# BLEModule.net
KiCad netlist of a schematic drawn in EAGLE
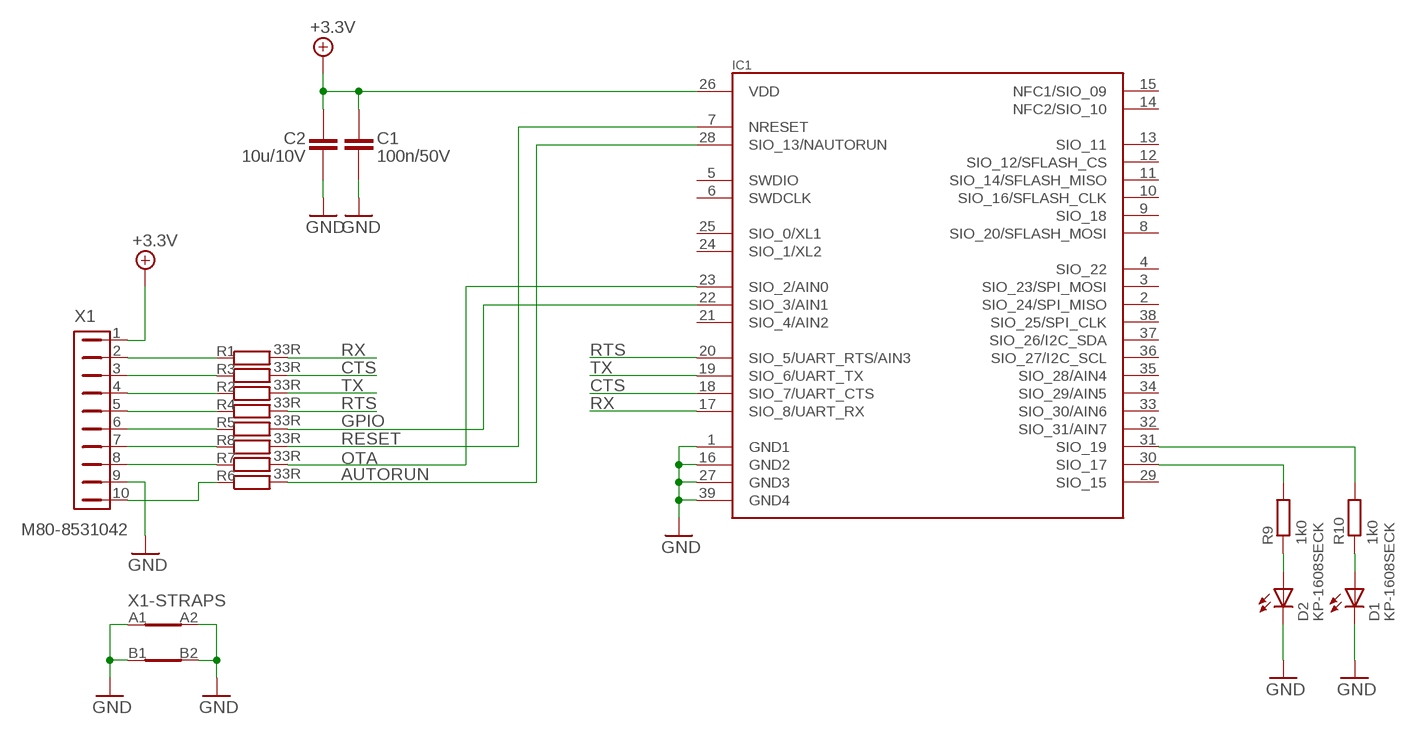
[diagram p0: schematic, sheet 1]

(export (version "E")
  (design (tool "Eeschema 10.0.6"))
  (components
    (comp (ref "C1")
      (value "100N/50V,X7R,+/-10%_0603R")
      (footprint "eagle-import:C0603R")
      (libsource (lib "eagle-import") (part "100N_0603R/50V,X7R,+/-10%"))
    )
    (comp (ref "C2")
      (value "10U/10V,X5R,+/-20%_0603R")
      (footprint "eagle-import:C0603R")
      (libsource (lib "eagle-import") (part "10U_0603R/10V,X5R,+/-20%"))
    )
    (comp (ref "D1")
      (value "KP-1608SECK")
      (footprint "eagle-import:0603")
      (libsource (lib "eagle-import") (part "KP-1608?SECK"))
    )
    (comp (ref "D2")
      (value "KP-1608SECK")
      (footprint "eagle-import:0603")
      (libsource (lib "eagle-import") (part "KP-1608?SECK"))
    )
    (comp (ref "IC1")
      (value "BL652-SC-01")
      (footprint "eagle-import:BL652-SA")
      (libsource (lib "eagle-import") (part "BL652-SC-01"))
    )
    (comp (ref "R1")
      (value "33R/0.1W,THICK_FILM,1%_0603R")
      (footprint "eagle-import:R0603R")
      (fields (field (name "COMPONENT_VALUE") "33R"))
      (libsource (lib "eagle-import") (part "33R_0603R/0.1W,THICK_FILM,1%"))
    )
    (comp (ref "R2")
      (value "33R/0.1W,THICK_FILM,1%_0603R")
      (footprint "eagle-import:R0603R")
      (fields (field (name "COMPONENT_VALUE") "33R"))
      (libsource (lib "eagle-import") (part "33R_0603R/0.1W,THICK_FILM,1%"))
    )
    (comp (ref "R3")
      (value "33R/0.1W,THICK_FILM,1%_0603R")
      (footprint "eagle-import:R0603R")
      (fields (field (name "COMPONENT_VALUE") "33R"))
      (libsource (lib "eagle-import") (part "33R_0603R/0.1W,THICK_FILM,1%"))
    )
    (comp (ref "R4")
      (value "33R/0.1W,THICK_FILM,1%_0603R")
      (footprint "eagle-import:R0603R")
      (fields (field (name "COMPONENT_VALUE") "33R"))
      (libsource (lib "eagle-import") (part "33R_0603R/0.1W,THICK_FILM,1%"))
    )
    (comp (ref "R5")
      (value "33R/0.1W,THICK_FILM,1%_0603R")
      (footprint "eagle-import:R0603R")
      (fields (field (name "COMPONENT_VALUE") "33R"))
      (libsource (lib "eagle-import") (part "33R_0603R/0.1W,THICK_FILM,1%"))
    )
    (comp (ref "R6")
      (value "33R/0.1W,THICK_FILM,1%_0603R")
      (footprint "eagle-import:R0603R")
      (fields (field (name "COMPONENT_VALUE") "33R"))
      (libsource (lib "eagle-import") (part "33R_0603R/0.1W,THICK_FILM,1%"))
    )
    (comp (ref "R7")
      (value "33R/0.1W,THICK_FILM,1%_0603R")
      (footprint "eagle-import:R0603R")
      (fields (field (name "COMPONENT_VALUE") "33R"))
      (libsource (lib "eagle-import") (part "33R_0603R/0.1W,THICK_FILM,1%"))
    )
    (comp (ref "R8")
      (value "33R/0.1W,THICK_FILM,1%_0603R")
      (footprint "eagle-import:R0603R")
      (fields (field (name "COMPONENT_VALUE") "33R"))
      (libsource (lib "eagle-import") (part "33R_0603R/0.1W,THICK_FILM,1%"))
    )
    (comp (ref "R9")
      (value "1K0/0.1W,THICK_FILM,1%_0603R")
      (footprint "eagle-import:R0603R")
      (libsource (lib "eagle-import") (part "1K0_0603R/0.1W,THICK_FILM,1%"))
    )
    (comp (ref "R10")
      (value "1K0/0.1W,THICK_FILM,1%_0603R")
      (footprint "eagle-import:R0603R")
      (libsource (lib "eagle-import") (part "1K0_0603R/0.1W,THICK_FILM,1%"))
    )
    (comp (ref "X1")
      (value "M80-8531042")
      (footprint "eagle-import:M80-85310-W_STRAPS")
      (fields (field (name "COMPONENT_VALUE") "M80-8531042"))
      (libsource (lib "eagle-import") (part "M80-?1042-W_STRAPS853"))
    )
  )
  (nets
    (net (code "1") (name "+3.3V") (class "Default")
      (node (ref "C1") (pin "2") (pinfunction "2_2") (pintype "passive"))
      (node (ref "C2") (pin "2") (pinfunction "2_2") (pintype "passive"))
      (node (ref "IC1") (pin "26") (pinfunction "VDD_26") (pintype "power_in"))
      (node (ref "X1") (pin "1") (pinfunction "1_1") (pintype "passive"))
    )
    (net (code "2") (name "/AUTORUN") (class "Default")
      (node (ref "IC1") (pin "28") (pinfunction "SIO_13/NAUTORUN_28") (pintype "bidirectional"))
      (node (ref "R6") (pin "2") (pinfunction "2_2") (pintype "passive"))
    )
    (net (code "3") (name "/CTS") (class "Default")
      (node (ref "IC1") (pin "18") (pinfunction "SIO_7/UART_CTS_18") (pintype "bidirectional"))
      (node (ref "R3") (pin "2") (pinfunction "2_2") (pintype "passive"))
    )
    (net (code "4") (name "/GPIO") (class "Default")
      (node (ref "IC1") (pin "22") (pinfunction "SIO_3/AIN1_22") (pintype "bidirectional"))
      (node (ref "R5") (pin "2") (pinfunction "2_2") (pintype "passive"))
    )
    (net (code "5") (name "/OTA") (class "Default")
      (node (ref "IC1") (pin "23") (pinfunction "SIO_2/AIN0_23") (pintype "bidirectional"))
      (node (ref "R7") (pin "2") (pinfunction "2_2") (pintype "passive"))
    )
    (net (code "6") (name "/RESET") (class "Default")
      (node (ref "IC1") (pin "7") (pinfunction "NRESET_7") (pintype "bidirectional"))
      (node (ref "R8") (pin "2") (pinfunction "2_2") (pintype "passive"))
    )
    (net (code "7") (name "/RTS") (class "Default")
      (node (ref "IC1") (pin "20") (pinfunction "SIO_5/UART_RTS/AIN3_20") (pintype "bidirectional"))
      (node (ref "R4") (pin "2") (pinfunction "2_2") (pintype "passive"))
    )
    (net (code "8") (name "/RX") (class "Default")
      (node (ref "IC1") (pin "17") (pinfunction "SIO_8/UART_RX_17") (pintype "bidirectional"))
      (node (ref "R1") (pin "2") (pinfunction "2_2") (pintype "passive"))
    )
    (net (code "9") (name "/TX") (class "Default")
      (node (ref "IC1") (pin "19") (pinfunction "SIO_6/UART_TX_19") (pintype "bidirectional"))
      (node (ref "R2") (pin "2") (pinfunction "2_2") (pintype "passive"))
    )
    (net (code "10") (name "GND") (class "Default")
      (node (ref "C1") (pin "1") (pinfunction "1_1") (pintype "passive"))
      (node (ref "C2") (pin "1") (pinfunction "1_1") (pintype "passive"))
      (node (ref "D1") (pin "2") (pinfunction "C_2") (pintype "passive"))
      (node (ref "D2") (pin "2") (pinfunction "C_2") (pintype "passive"))
      (node (ref "IC1") (pin "1") (pinfunction "GND1_1") (pintype "bidirectional"))
      (node (ref "IC1") (pin "16") (pinfunction "GND2_16") (pintype "bidirectional"))
      (node (ref "IC1") (pin "27") (pinfunction "GND3_27") (pintype "bidirectional"))
      (node (ref "IC1") (pin "39") (pinfunction "GND4_39") (pintype "bidirectional"))
      (node (ref "X1") (pin "9") (pinfunction "9_9") (pintype "passive"))
      (node (ref "X1") (pin "A1") (pinfunction "A1_A1") (pintype "passive"))
      (node (ref "X1") (pin "A2") (pinfunction "A2_A2") (pintype "passive"))
      (node (ref "X1") (pin "B1") (pinfunction "B1_B1") (pintype "passive"))
      (node (ref "X1") (pin "B2") (pinfunction "B2_B2") (pintype "passive"))
    )
    (net (code "11") (name "Net-(D1-A)") (class "Default")
      (node (ref "D1") (pin "1") (pinfunction "A_1") (pintype "passive"))
      (node (ref "R10") (pin "1") (pinfunction "1_1") (pintype "passive"))
    )
    (net (code "12") (name "Net-(D2-A)") (class "Default")
      (node (ref "D2") (pin "1") (pinfunction "A_1") (pintype "passive"))
      (node (ref "R9") (pin "1") (pinfunction "1_1") (pintype "passive"))
    )
    (net (code "13") (name "Net-(IC1-SIO_17)") (class "Default")
      (node (ref "IC1") (pin "30") (pinfunction "SIO_17_30") (pintype "bidirectional"))
      (node (ref "R9") (pin "2") (pinfunction "2_2") (pintype "passive"))
    )
    (net (code "14") (name "Net-(IC1-SIO_19)") (class "Default")
      (node (ref "IC1") (pin "31") (pinfunction "SIO_19_31") (pintype "bidirectional"))
      (node (ref "R10") (pin "2") (pinfunction "2_2") (pintype "passive"))
    )
    (net (code "15") (name "Net-(R1-Pad1)") (class "Default")
      (node (ref "R1") (pin "1") (pinfunction "1_1") (pintype "passive"))
      (node (ref "X1") (pin "2") (pinfunction "2_2") (pintype "passive"))
    )
    (net (code "16") (name "Net-(R2-Pad1)") (class "Default")
      (node (ref "R2") (pin "1") (pinfunction "1_1") (pintype "passive"))
      (node (ref "X1") (pin "4") (pinfunction "4_4") (pintype "passive"))
    )
    (net (code "17") (name "Net-(R3-Pad1)") (class "Default")
      (node (ref "R3") (pin "1") (pinfunction "1_1") (pintype "passive"))
      (node (ref "X1") (pin "3") (pinfunction "3_3") (pintype "passive"))
    )
    (net (code "18") (name "Net-(R4-Pad1)") (class "Default")
      (node (ref "R4") (pin "1") (pinfunction "1_1") (pintype "passive"))
      (node (ref "X1") (pin "5") (pinfunction "5_5") (pintype "passive"))
    )
    (net (code "19") (name "Net-(R5-Pad1)") (class "Default")
      (node (ref "R5") (pin "1") (pinfunction "1_1") (pintype "passive"))
      (node (ref "X1") (pin "6") (pinfunction "6_6") (pintype "passive"))
    )
    (net (code "20") (name "Net-(R6-Pad1)") (class "Default")
      (node (ref "R6") (pin "1") (pinfunction "1_1") (pintype "passive"))
      (node (ref "X1") (pin "10") (pinfunction "10_10") (pintype "passive"))
    )
    (net (code "21") (name "Net-(R7-Pad1)") (class "Default")
      (node (ref "R7") (pin "1") (pinfunction "1_1") (pintype "passive"))
      (node (ref "X1") (pin "8") (pinfunction "8_8") (pintype "passive"))
    )
    (net (code "22") (name "Net-(R8-Pad1)") (class "Default")
      (node (ref "R8") (pin "1") (pinfunction "1_1") (pintype "passive"))
      (node (ref "X1") (pin "7") (pinfunction "7_7") (pintype "passive"))
    )
    (net (code "23") (name "unconnected-(IC1-NFC1{slash}SIO_09-Pad15)") (class "Default")
      (node (ref "IC1") (pin "15") (pinfunction "NFC1/SIO_09_15") (pintype "bidirectional"))
    )
    (net (code "24") (name "unconnected-(IC1-NFC2{slash}SIO_10-Pad14)") (class "Default")
      (node (ref "IC1") (pin "14") (pinfunction "NFC2/SIO_10_14") (pintype "bidirectional"))
    )
    (net (code "25") (name "unconnected-(IC1-SIO_0{slash}XL1-Pad25)") (class "Default")
      (node (ref "IC1") (pin "25") (pinfunction "SIO_0/XL1_25") (pintype "bidirectional"))
    )
    (net (code "26") (name "unconnected-(IC1-SIO_1{slash}XL2-Pad24)") (class "Default")
      (node (ref "IC1") (pin "24") (pinfunction "SIO_1/XL2_24") (pintype "bidirectional"))
    )
    (net (code "27") (name "unconnected-(IC1-SIO_4{slash}AIN2-Pad21)") (class "Default")
      (node (ref "IC1") (pin "21") (pinfunction "SIO_4/AIN2_21") (pintype "bidirectional"))
    )
    (net (code "28") (name "unconnected-(IC1-SIO_11-Pad13)") (class "Default")
      (node (ref "IC1") (pin "13") (pinfunction "SIO_11_13") (pintype "bidirectional"))
    )
    (net (code "29") (name "unconnected-(IC1-SIO_12{slash}SFLASH_CS-Pad12)") (class "Default")
      (node (ref "IC1") (pin "12") (pinfunction "SIO_12/SFLASH_CS_12") (pintype "bidirectional"))
    )
    (net (code "30") (name "unconnected-(IC1-SIO_14{slash}SFLASH_MISO-Pad11)") (class "Default")
      (node (ref "IC1") (pin "11") (pinfunction "SIO_14/SFLASH_MISO_11") (pintype "bidirectional"))
    )
    (net (code "31") (name "unconnected-(IC1-SIO_15-Pad29)") (class "Default")
      (node (ref "IC1") (pin "29") (pinfunction "SIO_15_29") (pintype "bidirectional"))
    )
    (net (code "32") (name "unconnected-(IC1-SIO_16{slash}SFLASH_CLK-Pad10)") (class "Default")
      (node (ref "IC1") (pin "10") (pinfunction "SIO_16/SFLASH_CLK_10") (pintype "bidirectional"))
    )
    (net (code "33") (name "unconnected-(IC1-SIO_18-Pad9)") (class "Default")
      (node (ref "IC1") (pin "9") (pinfunction "SIO_18_9") (pintype "bidirectional"))
    )
    (net (code "34") (name "unconnected-(IC1-SIO_20{slash}SFLASH_MOSI-Pad8)") (class "Default")
      (node (ref "IC1") (pin "8") (pinfunction "SIO_20/SFLASH_MOSI_8") (pintype "bidirectional"))
    )
    (net (code "35") (name "unconnected-(IC1-SIO_22-Pad4)") (class "Default")
      (node (ref "IC1") (pin "4") (pinfunction "SIO_22_4") (pintype "bidirectional"))
    )
    (net (code "36") (name "unconnected-(IC1-SIO_23{slash}SPI_MOSI-Pad3)") (class "Default")
      (node (ref "IC1") (pin "3") (pinfunction "SIO_23/SPI_MOSI_3") (pintype "bidirectional"))
    )
    (net (code "37") (name "unconnected-(IC1-SIO_24{slash}SPI_MISO-Pad2)") (class "Default")
      (node (ref "IC1") (pin "2") (pinfunction "SIO_24/SPI_MISO_2") (pintype "bidirectional"))
    )
    (net (code "38") (name "unconnected-(IC1-SIO_25{slash}SPI_CLK-Pad38)") (class "Default")
      (node (ref "IC1") (pin "38") (pinfunction "SIO_25/SPI_CLK_38") (pintype "bidirectional"))
    )
    (net (code "39") (name "unconnected-(IC1-SIO_26{slash}I2C_SDA-Pad37)") (class "Default")
      (node (ref "IC1") (pin "37") (pinfunction "SIO_26/I2C_SDA_37") (pintype "bidirectional"))
    )
    (net (code "40") (name "unconnected-(IC1-SIO_27{slash}I2C_SCL-Pad36)") (class "Default")
      (node (ref "IC1") (pin "36") (pinfunction "SIO_27/I2C_SCL_36") (pintype "bidirectional"))
    )
    (net (code "41") (name "unconnected-(IC1-SIO_28{slash}AIN4-Pad35)") (class "Default")
      (node (ref "IC1") (pin "35") (pinfunction "SIO_28/AIN4_35") (pintype "bidirectional"))
    )
    (net (code "42") (name "unconnected-(IC1-SIO_29{slash}AIN5-Pad34)") (class "Default")
      (node (ref "IC1") (pin "34") (pinfunction "SIO_29/AIN5_34") (pintype "bidirectional"))
    )
    (net (code "43") (name "unconnected-(IC1-SIO_30{slash}AIN6-Pad33)") (class "Default")
      (node (ref "IC1") (pin "33") (pinfunction "SIO_30/AIN6_33") (pintype "bidirectional"))
    )
    (net (code "44") (name "unconnected-(IC1-SIO_31{slash}AIN7-Pad32)") (class "Default")
      (node (ref "IC1") (pin "32") (pinfunction "SIO_31/AIN7_32") (pintype "bidirectional"))
    )
    (net (code "45") (name "unconnected-(IC1-SWDCLK-Pad6)") (class "Default")
      (node (ref "IC1") (pin "6") (pinfunction "SWDCLK_6") (pintype "bidirectional"))
    )
    (net (code "46") (name "unconnected-(IC1-SWDIO-Pad5)") (class "Default")
      (node (ref "IC1") (pin "5") (pinfunction "SWDIO_5") (pintype "bidirectional"))
    )
  )
)
